# ISD1730.net
KiCad netlist of a schematic drawn in Altium Designer
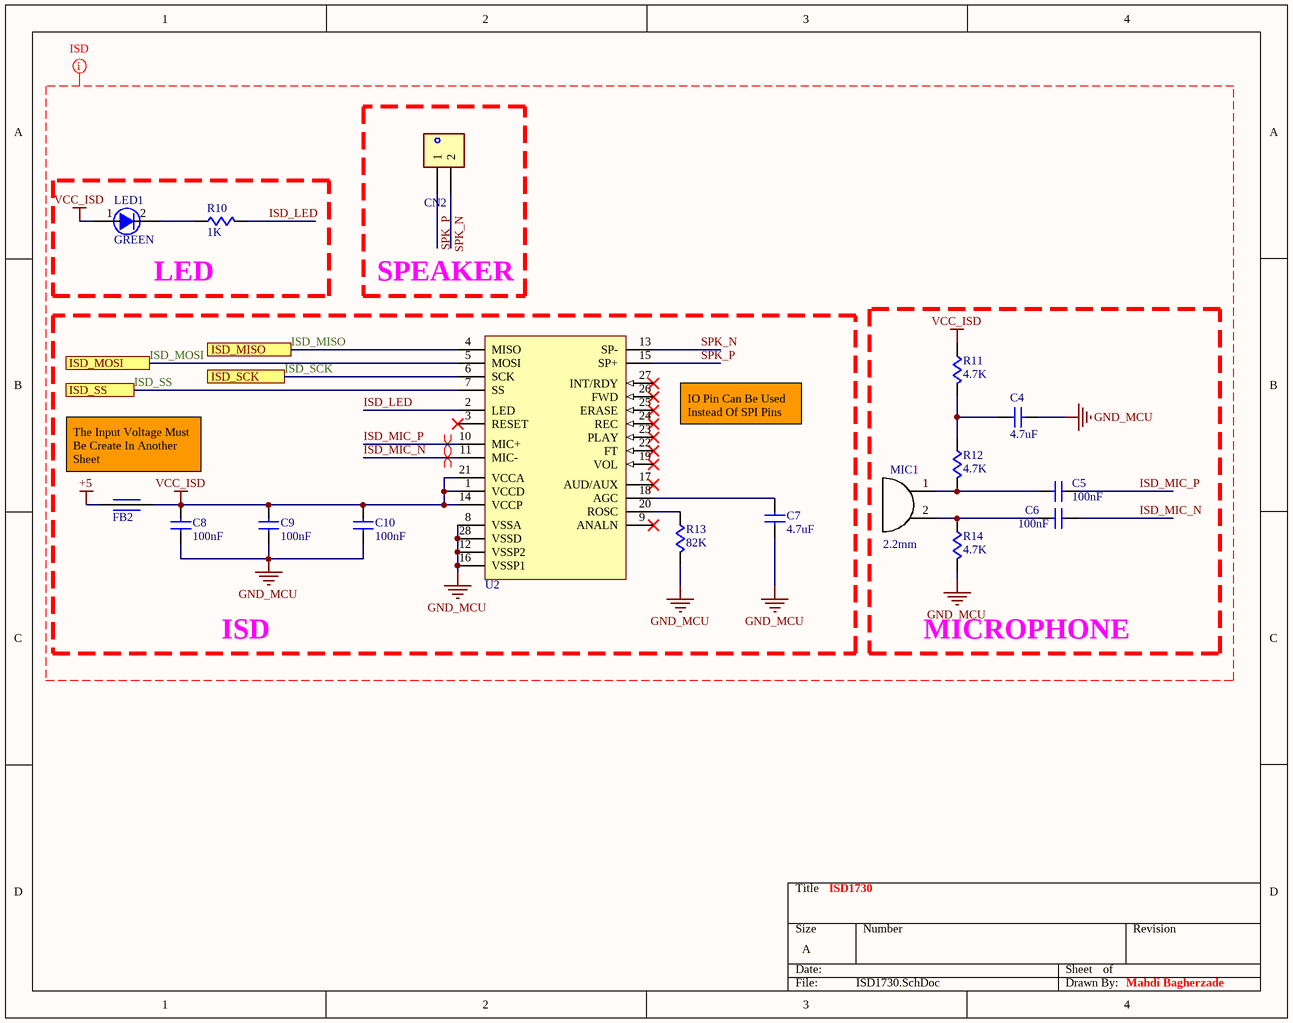
[diagram p0: ISD1730.SchDoc]

(export (version "E")
  (design (tool "Eeschema 10.0.6"))
  (components
    (comp (ref "C4")
      (value "4.7uF")
      (footprint "C-0805")
      (description "CAPACITOR")
      (fields
        (field (name "VOLTAGE") "50V")
        (field (name "TOLERANCE") "X7R")
        (field (name "PUBLISHER") "Mahdi Bagherzadeh")
      )
      (libsource (lib "Mahdi-Bagherzadeh") (part "CAP-CER"))
    )
    (comp (ref "C5")
      (value "100nF")
      (footprint "C-0805")
      (description "CAPACITOR")
      (fields
        (field (name "VOLTAGE") "50V")
        (field (name "TOLERANCE") "X7R")
        (field (name "PUBLISHER") "Mahdi Bagherzadeh")
      )
      (libsource (lib "Mahdi-Bagherzadeh") (part "CAP-CER"))
    )
    (comp (ref "C6")
      (value "100nF")
      (footprint "C-0805")
      (description "CAPACITOR")
      (fields
        (field (name "VOLTAGE") "50V")
        (field (name "TOLERANCE") "X7R")
        (field (name "PUBLISHER") "Mahdi Bagherzadeh")
      )
      (libsource (lib "Mahdi-Bagherzadeh") (part "CAP-CER"))
    )
    (comp (ref "C7")
      (value "4.7uF")
      (footprint "C-0805")
      (description "CAPACITOR")
      (fields
        (field (name "VOLTAGE") "50V")
        (field (name "TOLERANCE") "X7R")
        (field (name "PUBLISHER") "Mahdi Bagherzadeh")
      )
      (libsource (lib "Mahdi-Bagherzadeh") (part "CAP-CER"))
    )
    (comp (ref "C8")
      (value "100nF")
      (footprint "C-0805")
      (description "CAPACITOR")
      (fields
        (field (name "VOLTAGE") "50V")
        (field (name "TOLERANCE") "X7R")
        (field (name "PUBLISHER") "Mahdi Bagherzadeh")
      )
      (libsource (lib "Mahdi-Bagherzadeh") (part "CAP-CER"))
    )
    (comp (ref "C9")
      (value "100nF")
      (footprint "C-0805")
      (description "CAPACITOR")
      (fields
        (field (name "VOLTAGE") "50V")
        (field (name "TOLERANCE") "X7R")
        (field (name "PUBLISHER") "Mahdi Bagherzadeh")
      )
      (libsource (lib "Mahdi-Bagherzadeh") (part "CAP-CER"))
    )
    (comp (ref "C10")
      (value "100nF")
      (footprint "C-0805")
      (description "CAPACITOR")
      (fields
        (field (name "VOLTAGE") "50V")
        (field (name "TOLERANCE") "X7R")
        (field (name "PUBLISHER") "Mahdi Bagherzadeh")
      )
      (libsource (lib "Mahdi-Bagherzadeh") (part "CAP-CER"))
    )
    (comp (ref "CN2")
      (value "Connector XH-2-Straight-THD-2.54mm")
      (footprint "XH-2")
      (description "CONNECTOR")
      (fields (field (name "PUBLISHER") "Mahdi Bagherzadeh"))
      (libsource (lib "Mahdi-Bagherzadeh") (part "CN-2pin"))
    )
    (comp (ref "FB2")
      (value "Ferrite Bead SMD")
      (footprint "FB-0805")
      (description "INDUCATOR")
      (fields (field (name "PUBLISHER") "Mahdi Bagherzadeh"))
      (libsource (lib "Mahdi-Bagherzadeh") (part "FERRITE BEAD"))
    )
    (comp (ref "LED1")
      (value "LED GREEN-1206-SMD")
      (footprint "LED-1206-Y")
      (description "LED")
      (fields (field (name "COLOR") "GREEN") (field (name "PUBLISHER") "Mahdi Bagherzadeh"))
      (libsource (lib "Mahdi-Bagherzadeh") (part "LED"))
    )
    (comp (ref "MIC1")
      (value "Mic 2.2mm-THD")
      (footprint "MIC-2.2mm")
      (description "MIC")
      (fields (field (name "SIZE") "2.2mm") (field (name "PUBLISHER") "Mahdi Bagherzadeh"))
      (libsource (lib "Mahdi-Bagherzadeh") (part "MIC"))
    )
    (comp (ref "R10")
      (value "1K")
      (footprint "R-0805")
      (description "RESISTOR")
      (fields
        (field (name "POWER") "1/8W")
        (field (name "TOLERANCE") "5%")
        (field (name "PUBLISHER") "Mahdi Bagherzadeh")
      )
      (libsource (lib "Mahdi-Bagherzadeh") (part "RES"))
    )
    (comp (ref "R11")
      (value "4.7K")
      (footprint "R-0805")
      (description "RESISTOR")
      (fields
        (field (name "POWER") "1/8W")
        (field (name "TOLERANCE") "5%")
        (field (name "PUBLISHER") "Mahdi Bagherzadeh")
      )
      (libsource (lib "Mahdi-Bagherzadeh") (part "RES"))
    )
    (comp (ref "R12")
      (value "4.7K")
      (footprint "R-0805")
      (description "RESISTOR")
      (fields
        (field (name "POWER") "1/8W")
        (field (name "TOLERANCE") "5%")
        (field (name "PUBLISHER") "Mahdi Bagherzadeh")
      )
      (libsource (lib "Mahdi-Bagherzadeh") (part "RES"))
    )
    (comp (ref "R13")
      (value "82K")
      (footprint "R-0805")
      (description "RESISTOR")
      (fields
        (field (name "POWER") "1/8W")
        (field (name "TOLERANCE") "5%")
        (field (name "PUBLISHER") "Mahdi Bagherzadeh")
      )
      (libsource (lib "Mahdi-Bagherzadeh") (part "RES"))
    )
    (comp (ref "R14")
      (value "4.7K")
      (footprint "R-0805")
      (description "RESISTOR")
      (fields
        (field (name "POWER") "1/8W")
        (field (name "TOLERANCE") "5%")
        (field (name "PUBLISHER") "Mahdi Bagherzadeh")
      )
      (libsource (lib "Mahdi-Bagherzadeh") (part "RES"))
    )
    (comp (ref "U2")
      (value "IC ISD1730-SMD")
      (footprint "DIP28-wide")
      (description "IC")
      (fields (field (name "PUBLISHER") "Mahdi Bagherzadeh"))
      (libsource (lib "Mahdi-Bagherzadeh") (part "ISD1730"))
    )
  )
  (nets
    (net (code "1") (name "+5") (class "Default")
      (node (ref "FB2") (pin "1") (pinfunction "1_1") (pintype "passive"))
    )
    (net (code "2") (name "/ISD_LED") (class "Default")
      (node (ref "R10") (pin "2") (pinfunction "2_2") (pintype "passive"))
      (node (ref "U2") (pin "2") (pinfunction "LED_2") (pintype "passive"))
    )
    (net (code "3") (name "/ISD_MIC_N") (class "Default")
      (node (ref "C6") (pin "2") (pinfunction "2_2") (pintype "passive"))
      (node (ref "U2") (pin "11") (pinfunction "MIC-_11") (pintype "passive"))
    )
    (net (code "4") (name "/ISD_MIC_P") (class "Default")
      (node (ref "C5") (pin "2") (pinfunction "2_2") (pintype "passive"))
      (node (ref "U2") (pin "10") (pinfunction "MIC+_10") (pintype "passive"))
    )
    (net (code "5") (name "/ISD_MISO") (class "Default")
      (node (ref "U2") (pin "4") (pinfunction "MISO_4") (pintype "passive"))
    )
    (net (code "6") (name "/ISD_MOSI") (class "Default")
      (node (ref "U2") (pin "5") (pinfunction "MOSI_5") (pintype "passive"))
    )
    (net (code "7") (name "/ISD_SCK") (class "Default")
      (node (ref "U2") (pin "6") (pinfunction "SCK_6") (pintype "passive"))
    )
    (net (code "8") (name "/ISD_SS") (class "Default")
      (node (ref "U2") (pin "7") (pinfunction "SS_7") (pintype "passive"))
    )
    (net (code "9") (name "/SPK_N") (class "Default")
      (node (ref "CN2") (pin "2") (pinfunction "2_2") (pintype "passive"))
      (node (ref "U2") (pin "13") (pinfunction "SP-_13") (pintype "passive"))
    )
    (net (code "10") (name "/SPK_P") (class "Default")
      (node (ref "CN2") (pin "1") (pinfunction "1_1") (pintype "passive"))
      (node (ref "U2") (pin "15") (pinfunction "SP+_15") (pintype "passive"))
    )
    (net (code "11") (name "GND_MCU") (class "Default")
      (node (ref "C10") (pin "2") (pinfunction "2_2") (pintype "passive"))
      (node (ref "C4") (pin "2") (pinfunction "2_2") (pintype "passive"))
      (node (ref "C7") (pin "2") (pinfunction "2_2") (pintype "passive"))
      (node (ref "C8") (pin "2") (pinfunction "2_2") (pintype "passive"))
      (node (ref "C9") (pin "2") (pinfunction "2_2") (pintype "passive"))
      (node (ref "R13") (pin "2") (pinfunction "2_2") (pintype "passive"))
      (node (ref "R14") (pin "2") (pinfunction "2_2") (pintype "passive"))
      (node (ref "U2") (pin "12") (pinfunction "VSSP2_12") (pintype "power_in"))
      (node (ref "U2") (pin "16") (pinfunction "VSSP1_16") (pintype "power_in"))
      (node (ref "U2") (pin "28") (pinfunction "VSSD_28") (pintype "power_in"))
      (node (ref "U2") (pin "8") (pinfunction "VSSA_8") (pintype "power_in"))
    )
    (net (code "12") (name "Net-(C4-Pad1)") (class "Default")
      (node (ref "C4") (pin "1") (pinfunction "1_1") (pintype "passive"))
      (node (ref "R11") (pin "2") (pinfunction "2_2") (pintype "passive"))
      (node (ref "R12") (pin "1") (pinfunction "1_1") (pintype "passive"))
    )
    (net (code "13") (name "Net-(C5-Pad1)") (class "Default")
      (node (ref "C5") (pin "1") (pinfunction "1_1") (pintype "passive"))
      (node (ref "MIC1") (pin "1") (pinfunction "1_1") (pintype "passive"))
      (node (ref "R12") (pin "2") (pinfunction "2_2") (pintype "passive"))
    )
    (net (code "14") (name "Net-(C6-Pad1)") (class "Default")
      (node (ref "C6") (pin "1") (pinfunction "1_1") (pintype "passive"))
      (node (ref "MIC1") (pin "2") (pinfunction "2_2") (pintype "passive"))
      (node (ref "R14") (pin "1") (pinfunction "1_1") (pintype "passive"))
    )
    (net (code "15") (name "Net-(LED1-C)") (class "Default")
      (node (ref "LED1") (pin "2") (pinfunction "C_2") (pintype "passive"))
      (node (ref "R10") (pin "1") (pinfunction "1_1") (pintype "passive"))
    )
    (net (code "16") (name "Net-(U2-AGC)") (class "Default")
      (node (ref "C7") (pin "1") (pinfunction "1_1") (pintype "passive"))
      (node (ref "U2") (pin "18") (pinfunction "AGC_18") (pintype "passive"))
    )
    (net (code "17") (name "Net-(U2-ROSC)") (class "Default")
      (node (ref "R13") (pin "1") (pinfunction "1_1") (pintype "passive"))
      (node (ref "U2") (pin "20") (pinfunction "ROSC_20") (pintype "passive"))
    )
    (net (code "18") (name "VCC_ISD") (class "Default")
      (node (ref "C10") (pin "1") (pinfunction "1_1") (pintype "passive"))
      (node (ref "C8") (pin "1") (pinfunction "1_1") (pintype "passive"))
      (node (ref "C9") (pin "1") (pinfunction "1_1") (pintype "passive"))
      (node (ref "FB2") (pin "2") (pinfunction "2_2") (pintype "passive"))
      (node (ref "LED1") (pin "1") (pinfunction "A_1") (pintype "passive"))
      (node (ref "R11") (pin "1") (pinfunction "1_1") (pintype "passive"))
      (node (ref "U2") (pin "1") (pinfunction "VCCD_1") (pintype "power_in"))
      (node (ref "U2") (pin "14") (pinfunction "VCCP_14") (pintype "power_in"))
      (node (ref "U2") (pin "21") (pinfunction "VCCA_21") (pintype "power_in"))
    )
    (net (code "19") (name "unconnected-(U2-ANALN-Pad9)") (class "Default")
      (node (ref "U2") (pin "9") (pinfunction "ANALN_9") (pintype "passive+no_connect"))
    )
    (net (code "20") (name "unconnected-(U2-AUD{slash}AUX-Pad17)") (class "Default")
      (node (ref "U2") (pin "17") (pinfunction "AUD/AUX_17") (pintype "passive+no_connect"))
    )
    (net (code "21") (name "unconnected-(U2-ERASE-Pad25)") (class "Default")
      (node (ref "U2") (pin "25") (pinfunction "ERASE_25") (pintype "input+no_connect"))
    )
    (net (code "22") (name "unconnected-(U2-FT-Pad22)") (class "Default")
      (node (ref "U2") (pin "22") (pinfunction "FT_22") (pintype "input+no_connect"))
    )
    (net (code "23") (name "unconnected-(U2-FWD-Pad26)") (class "Default")
      (node (ref "U2") (pin "26") (pinfunction "FWD_26") (pintype "input+no_connect"))
    )
    (net (code "24") (name "unconnected-(U2-INT{slash}RDY-Pad27)") (class "Default")
      (node (ref "U2") (pin "27") (pinfunction "INT/RDY_27") (pintype "input+no_connect"))
    )
    (net (code "25") (name "unconnected-(U2-PLAY-Pad23)") (class "Default")
      (node (ref "U2") (pin "23") (pinfunction "PLAY_23") (pintype "input+no_connect"))
    )
    (net (code "26") (name "unconnected-(U2-REC-Pad24)") (class "Default")
      (node (ref "U2") (pin "24") (pinfunction "REC_24") (pintype "input+no_connect"))
    )
    (net (code "27") (name "unconnected-(U2-RESET-Pad3)") (class "Default")
      (node (ref "U2") (pin "3") (pinfunction "RESET_3") (pintype "passive+no_connect"))
    )
    (net (code "28") (name "unconnected-(U2-VOL-Pad19)") (class "Default")
      (node (ref "U2") (pin "19") (pinfunction "VOL_19") (pintype "input+no_connect"))
    )
  )
)
